# PCIe_Connector.net
KiCad netlist of a schematic drawn in Altium Designer
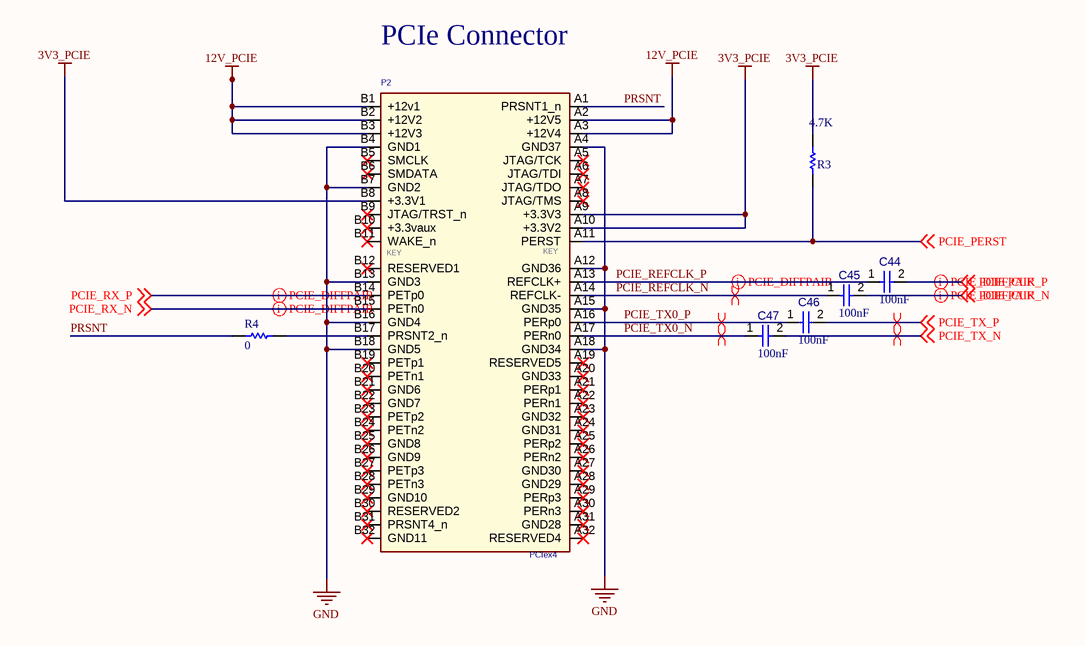
[diagram p0: PCIe_Connector.SchDoc]

(export (version "E")
  (design (tool "Eeschema 10.0.6"))
  (components
    (comp (ref "C44")
      (value "100nF")
      (footprint "CAPC1005X56X25LL10T15")
      (description "Chip Capacitor, 0.1 uF, +/- 5%, 16 V, 0402 (1005 Metric)")
      (fields (field (name "TOLERANCE") "5%") (field (name "Comment") "Capacitor 0.1 uF +/- 5% 16 V 0402"))
      (libsource (lib "Lasse Johnsen") (part "CAP-NP-2"))
    )
    (comp (ref "C45")
      (value "100nF")
      (footprint "CAPC1005X56X25LL10T15")
      (description "Chip Capacitor, 0.1 uF, +/- 5%, 16 V, 0402 (1005 Metric)")
      (fields (field (name "TOLERANCE") "5%") (field (name "Comment") "Capacitor 0.1 uF +/- 5% 16 V 0402"))
      (libsource (lib "Lasse Johnsen") (part "CAP-NP-2"))
    )
    (comp (ref "C46")
      (value "100nF")
      (footprint "CAPC1005X56X25LL10T15")
      (description "Chip Capacitor, 0.1 uF, +/- 5%, 16 V, 0402 (1005 Metric)")
      (fields (field (name "TOLERANCE") "5%") (field (name "Comment") "Capacitor 0.1 uF +/- 5% 16 V 0402"))
      (libsource (lib "Lasse Johnsen") (part "CAP-NP-2"))
    )
    (comp (ref "C47")
      (value "100nF")
      (footprint "CAPC1005X56X25LL10T15")
      (description "Chip Capacitor, 0.1 uF, +/- 5%, 16 V, 0402 (1005 Metric)")
      (fields (field (name "TOLERANCE") "5%") (field (name "Comment") "Capacitor 0.1 uF +/- 5% 16 V 0402"))
      (libsource (lib "Lasse Johnsen") (part "CAP-NP-2"))
    )
    (comp (ref "P2")
      (value "PCIex4")
      (footprint "PCIE_4LANE_EDGE")
      (description "PCIE x4 Edge Connector,OrCAD Symbol,NC")
      (fields (field (name "PART NUMBER") "451") (field (name "MANUFACTURER") "NA"))
      (libsource (lib "Connectors") (part "PCIex4"))
    )
    (comp (ref "R3")
      (value "4.7K")
      (footprint "RESC1005X40X25LL05T05")
      (description "Chip Resistor, 4.7 KOhm, +/- 1%, 0.1 W, -55 to 155 degC, 0402 (1005 Metric), RoHS, Tape and Reel")
      (fields (field (name "TOLERANCE") "1%") (field (name "PARTNUMBER") "ERJ-2RKF4701X"))
      (libsource (lib "Altium Content Vault") (part "RES-2"))
    )
    (comp (ref "R4")
      (value "0")
      (footprint "RESC1005X40X25ML05T10")
      (description "Chip Resistor, 0 Ohm, 0.063 W, -55 to 155 degC, 0402 (1005 Metric)")
      (fields (field (name "POWER") "63mW") (field (name "Comment") "Resistor 0R 0402 63 mW"))
      (libsource (lib "Lasse Johnsen") (part "RES-2"))
    )
  )
  (nets
    (net (code "1") (name "/PCIE_REFCLK_N") (class "Default")
      (node (ref "C45") (pin "1") (pinfunction "1_1") (pintype "passive"))
      (node (ref "P2") (pin "A14") (pinfunction "REFCLK-_A14") (pintype "passive"))
    )
    (net (code "2") (name "/PCIE_REFCLK_P") (class "Default")
      (node (ref "C44") (pin "1") (pinfunction "1_1") (pintype "passive"))
      (node (ref "P2") (pin "A13") (pinfunction "REFCLK+_A13") (pintype "passive"))
    )
    (net (code "3") (name "/PCIE_TX0_N") (class "Default")
      (node (ref "C47") (pin "1") (pinfunction "1_1") (pintype "passive"))
      (node (ref "P2") (pin "A17") (pinfunction "PERn0_A17") (pintype "passive"))
    )
    (net (code "4") (name "/PCIE_TX0_P") (class "Default")
      (node (ref "C46") (pin "1") (pinfunction "1_1") (pintype "passive"))
      (node (ref "P2") (pin "A16") (pinfunction "PERp0_A16") (pintype "passive"))
    )
    (net (code "5") (name "/PRSNT") (class "Default")
      (node (ref "P2") (pin "A1") (pinfunction "PRSNT1_n_A1") (pintype "passive"))
      (node (ref "R4") (pin "1") (pinfunction "1_1") (pintype "passive"))
    )
    (net (code "6") (name "3V3_PCIE") (class "Default")
      (node (ref "P2") (pin "A10") (pinfunction "+3.3V2_A10") (pintype "passive"))
      (node (ref "P2") (pin "A9") (pinfunction "+3.3V3_A9") (pintype "passive"))
      (node (ref "P2") (pin "B8") (pinfunction "+3.3V1_B8") (pintype "power_in"))
      (node (ref "R3") (pin "2") (pinfunction "2_2") (pintype "passive"))
    )
    (net (code "7") (name "12V_PCIE") (class "Default")
      (node (ref "P2") (pin "A2") (pinfunction "+12V5_A2") (pintype "passive"))
      (node (ref "P2") (pin "A3") (pinfunction "+12V4_A3") (pintype "passive"))
      (node (ref "P2") (pin "B1") (pinfunction "+12v1_B1") (pintype "power_in"))
      (node (ref "P2") (pin "B2") (pinfunction "+12V2_B2") (pintype "power_in"))
      (node (ref "P2") (pin "B3") (pinfunction "+12V3_B3") (pintype "power_in"))
    )
    (net (code "8") (name "GND") (class "Default")
      (node (ref "P2") (pin "A12") (pinfunction "GND36_A12") (pintype "power_in"))
      (node (ref "P2") (pin "A15") (pinfunction "GND35_A15") (pintype "power_in"))
      (node (ref "P2") (pin "A18") (pinfunction "GND34_A18") (pintype "power_in"))
      (node (ref "P2") (pin "A4") (pinfunction "GND37_A4") (pintype "power_in"))
      (node (ref "P2") (pin "B13") (pinfunction "GND3_B13") (pintype "power_in"))
      (node (ref "P2") (pin "B16") (pinfunction "GND4_B16") (pintype "power_in"))
      (node (ref "P2") (pin "B18") (pinfunction "GND5_B18") (pintype "power_in"))
      (node (ref "P2") (pin "B4") (pinfunction "GND1_B4") (pintype "power_in"))
      (node (ref "P2") (pin "B7") (pinfunction "GND2_B7") (pintype "power_in"))
    )
    (net (code "9") (name "Net-(P2-PRSNT2_n)") (class "Default")
      (node (ref "P2") (pin "B17") (pinfunction "PRSNT2_n_B17") (pintype "passive"))
      (node (ref "R4") (pin "2") (pinfunction "2_2") (pintype "passive"))
    )
    (net (code "10") (name "PCIE_CLK_N") (class "Default")
      (node (ref "C45") (pin "2") (pinfunction "2_2") (pintype "passive"))
    )
    (net (code "11") (name "PCIE_CLK_P") (class "Default")
      (node (ref "C44") (pin "2") (pinfunction "2_2") (pintype "passive"))
    )
    (net (code "12") (name "PCIE_PERST") (class "Default")
      (node (ref "P2") (pin "A11") (pinfunction "PERST_A11") (pintype "passive"))
      (node (ref "R3") (pin "1") (pinfunction "1_1") (pintype "passive"))
    )
    (net (code "13") (name "PCIE_RX_N") (class "Default")
      (node (ref "P2") (pin "B15") (pinfunction "PETn0_B15") (pintype "passive"))
    )
    (net (code "14") (name "PCIE_RX_P") (class "Default")
      (node (ref "P2") (pin "B14") (pinfunction "PETp0_B14") (pintype "passive"))
    )
    (net (code "15") (name "PCIE_TX_N") (class "Default")
      (node (ref "C47") (pin "2") (pinfunction "2_2") (pintype "passive"))
    )
    (net (code "16") (name "PCIE_TX_P") (class "Default")
      (node (ref "C46") (pin "2") (pinfunction "2_2") (pintype "passive"))
    )
    (net (code "17") (name "unconnected-(P2-+3.3vaux-PadB10)") (class "Default")
      (node (ref "P2") (pin "B10") (pinfunction "+3.3vaux_B10") (pintype "passive+no_connect"))
    )
    (net (code "18") (name "unconnected-(P2-GND6-PadB21)") (class "Default")
      (node (ref "P2") (pin "B21") (pinfunction "GND6_B21") (pintype "power_in+no_connect"))
    )
    (net (code "19") (name "unconnected-(P2-GND7-PadB22)") (class "Default")
      (node (ref "P2") (pin "B22") (pinfunction "GND7_B22") (pintype "power_in+no_connect"))
    )
    (net (code "20") (name "unconnected-(P2-GND8-PadB25)") (class "Default")
      (node (ref "P2") (pin "B25") (pinfunction "GND8_B25") (pintype "power_in+no_connect"))
    )
    (net (code "21") (name "unconnected-(P2-GND9-PadB26)") (class "Default")
      (node (ref "P2") (pin "B26") (pinfunction "GND9_B26") (pintype "power_in+no_connect"))
    )
    (net (code "22") (name "unconnected-(P2-GND10-PadB29)") (class "Default")
      (node (ref "P2") (pin "B29") (pinfunction "GND10_B29") (pintype "power_in+no_connect"))
    )
    (net (code "23") (name "unconnected-(P2-GND11-PadB32)") (class "Default")
      (node (ref "P2") (pin "B32") (pinfunction "GND11_B32") (pintype "power_in+no_connect"))
    )
    (net (code "24") (name "unconnected-(P2-GND28-PadA31)") (class "Default")
      (node (ref "P2") (pin "A31") (pinfunction "GND28_A31") (pintype "power_in+no_connect"))
    )
    (net (code "25") (name "unconnected-(P2-GND29-PadA28)") (class "Default")
      (node (ref "P2") (pin "A28") (pinfunction "GND29_A28") (pintype "power_in+no_connect"))
    )
    (net (code "26") (name "unconnected-(P2-GND30-PadA27)") (class "Default")
      (node (ref "P2") (pin "A27") (pinfunction "GND30_A27") (pintype "power_in+no_connect"))
    )
    (net (code "27") (name "unconnected-(P2-GND31-PadA24)") (class "Default")
      (node (ref "P2") (pin "A24") (pinfunction "GND31_A24") (pintype "power_in+no_connect"))
    )
    (net (code "28") (name "unconnected-(P2-GND32-PadA23)") (class "Default")
      (node (ref "P2") (pin "A23") (pinfunction "GND32_A23") (pintype "power_in+no_connect"))
    )
    (net (code "29") (name "unconnected-(P2-GND33-PadA20)") (class "Default")
      (node (ref "P2") (pin "A20") (pinfunction "GND33_A20") (pintype "power_in+no_connect"))
    )
    (net (code "30") (name "unconnected-(P2-JTAG{slash}TCK-PadA5)") (class "Default")
      (node (ref "P2") (pin "A5") (pinfunction "JTAG/TCK_A5") (pintype "passive+no_connect"))
    )
    (net (code "31") (name "unconnected-(P2-JTAG{slash}TDI-PadA6)") (class "Default")
      (node (ref "P2") (pin "A6") (pinfunction "JTAG/TDI_A6") (pintype "passive+no_connect"))
    )
    (net (code "32") (name "unconnected-(P2-JTAG{slash}TDO-PadA7)") (class "Default")
      (node (ref "P2") (pin "A7") (pinfunction "JTAG/TDO_A7") (pintype "passive+no_connect"))
    )
    (net (code "33") (name "unconnected-(P2-JTAG{slash}TMS-PadA8)") (class "Default")
      (node (ref "P2") (pin "A8") (pinfunction "JTAG/TMS_A8") (pintype "passive+no_connect"))
    )
    (net (code "34") (name "unconnected-(P2-JTAG{slash}TRST_n-PadB9)") (class "Default")
      (node (ref "P2") (pin "B9") (pinfunction "JTAG/TRST_n_B9") (pintype "passive+no_connect"))
    )
    (net (code "35") (name "unconnected-(P2-PERn1-PadA22)") (class "Default")
      (node (ref "P2") (pin "A22") (pinfunction "PERn1_A22") (pintype "passive+no_connect"))
    )
    (net (code "36") (name "unconnected-(P2-PERn2-PadA26)") (class "Default")
      (node (ref "P2") (pin "A26") (pinfunction "PERn2_A26") (pintype "passive+no_connect"))
    )
    (net (code "37") (name "unconnected-(P2-PERn3-PadA30)") (class "Default")
      (node (ref "P2") (pin "A30") (pinfunction "PERn3_A30") (pintype "passive+no_connect"))
    )
    (net (code "38") (name "unconnected-(P2-PERp1-PadA21)") (class "Default")
      (node (ref "P2") (pin "A21") (pinfunction "PERp1_A21") (pintype "passive+no_connect"))
    )
    (net (code "39") (name "unconnected-(P2-PERp2-PadA25)") (class "Default")
      (node (ref "P2") (pin "A25") (pinfunction "PERp2_A25") (pintype "passive+no_connect"))
    )
    (net (code "40") (name "unconnected-(P2-PERp3-PadA29)") (class "Default")
      (node (ref "P2") (pin "A29") (pinfunction "PERp3_A29") (pintype "passive+no_connect"))
    )
    (net (code "41") (name "unconnected-(P2-PETn1-PadB20)") (class "Default")
      (node (ref "P2") (pin "B20") (pinfunction "PETn1_B20") (pintype "passive+no_connect"))
    )
    (net (code "42") (name "unconnected-(P2-PETn2-PadB24)") (class "Default")
      (node (ref "P2") (pin "B24") (pinfunction "PETn2_B24") (pintype "passive+no_connect"))
    )
    (net (code "43") (name "unconnected-(P2-PETn3-PadB28)") (class "Default")
      (node (ref "P2") (pin "B28") (pinfunction "PETn3_B28") (pintype "passive+no_connect"))
    )
    (net (code "44") (name "unconnected-(P2-PETp1-PadB19)") (class "Default")
      (node (ref "P2") (pin "B19") (pinfunction "PETp1_B19") (pintype "passive+no_connect"))
    )
    (net (code "45") (name "unconnected-(P2-PETp2-PadB23)") (class "Default")
      (node (ref "P2") (pin "B23") (pinfunction "PETp2_B23") (pintype "passive+no_connect"))
    )
    (net (code "46") (name "unconnected-(P2-PETp3-PadB27)") (class "Default")
      (node (ref "P2") (pin "B27") (pinfunction "PETp3_B27") (pintype "passive+no_connect"))
    )
    (net (code "47") (name "unconnected-(P2-PRSNT4_n-PadB31)") (class "Default")
      (node (ref "P2") (pin "B31") (pinfunction "PRSNT4_n_B31") (pintype "passive+no_connect"))
    )
    (net (code "48") (name "unconnected-(P2-RESERVED1-PadB12)") (class "Default")
      (node (ref "P2") (pin "B12") (pinfunction "RESERVED1_B12") (pintype "passive+no_connect"))
    )
    (net (code "49") (name "unconnected-(P2-RESERVED2-PadB30)") (class "Default")
      (node (ref "P2") (pin "B30") (pinfunction "RESERVED2_B30") (pintype "passive+no_connect"))
    )
    (net (code "50") (name "unconnected-(P2-RESERVED4-PadA32)") (class "Default")
      (node (ref "P2") (pin "A32") (pinfunction "RESERVED4_A32") (pintype "passive+no_connect"))
    )
    (net (code "51") (name "unconnected-(P2-RESERVED5-PadA19)") (class "Default")
      (node (ref "P2") (pin "A19") (pinfunction "RESERVED5_A19") (pintype "passive+no_connect"))
    )
    (net (code "52") (name "unconnected-(P2-SMCLK-PadB5)") (class "Default")
      (node (ref "P2") (pin "B5") (pinfunction "SMCLK_B5") (pintype "passive+no_connect"))
    )
    (net (code "53") (name "unconnected-(P2-SMDATA-PadB6)") (class "Default")
      (node (ref "P2") (pin "B6") (pinfunction "SMDATA_B6") (pintype "passive+no_connect"))
    )
    (net (code "54") (name "unconnected-(P2-WAKE_n-PadB11)") (class "Default")
      (node (ref "P2") (pin "B11") (pinfunction "WAKE_n_B11") (pintype "passive+no_connect"))
    )
  )
)
